# picusb.net
KiCad netlist of a schematic drawn in EAGLE
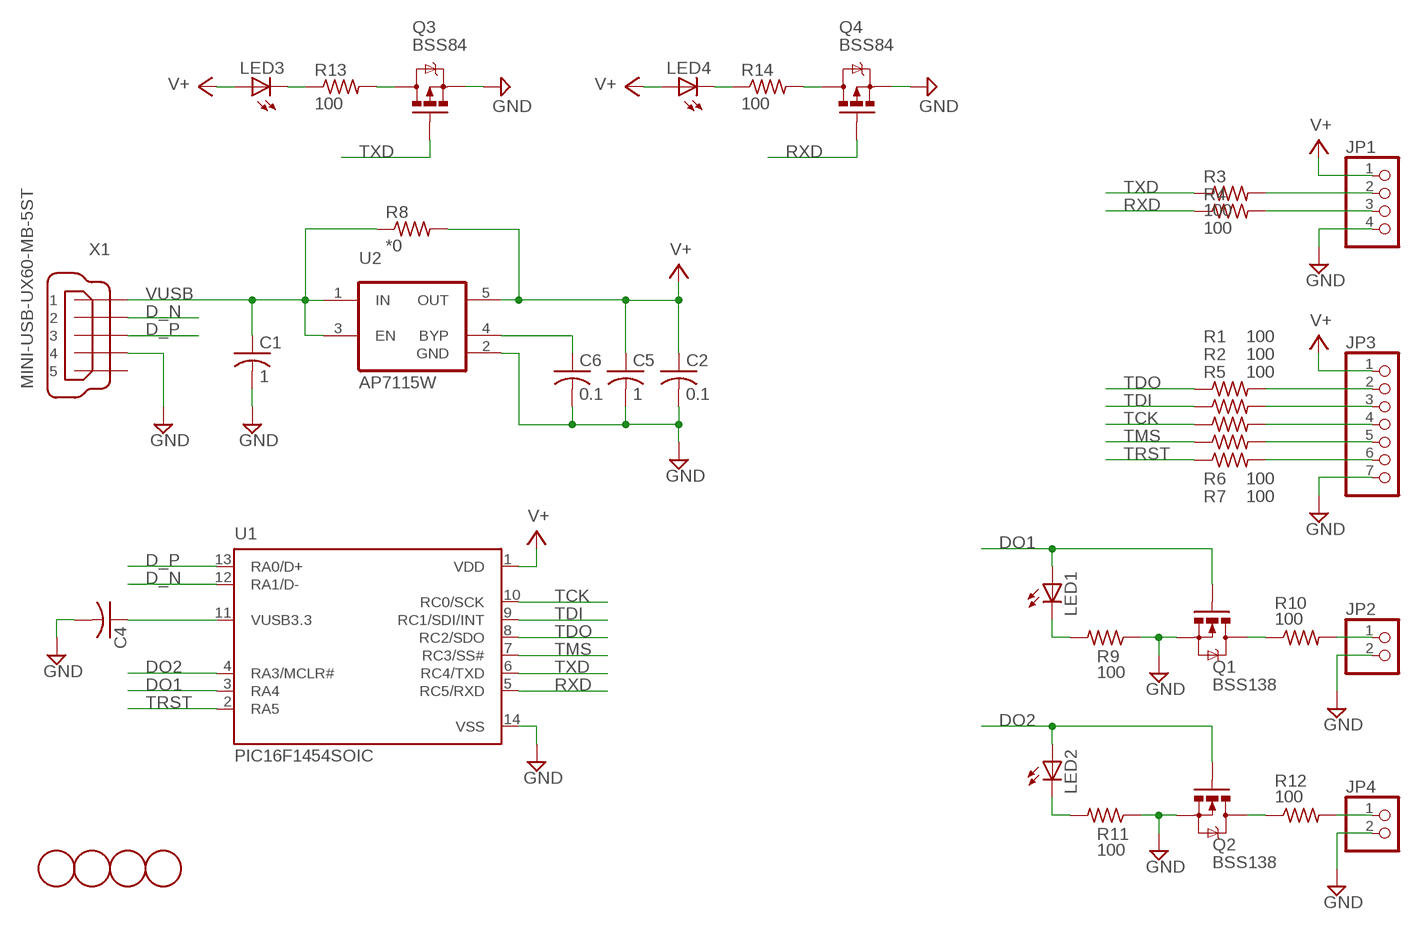
[diagram p0: schematic, sheet 1]

(export (version "E")
  (design (tool "Eeschema 10.0.6"))
  (components
    (comp (ref "C1")
      (value "1")
      (footprint "eagle-import:C0805")
      (libsource (lib "eagle-import") (part "C-USC0805"))
    )
    (comp (ref "C2")
      (value "0.1")
      (footprint "eagle-import:C0805")
      (libsource (lib "eagle-import") (part "C-USC0805"))
    )
    (comp (ref "C4")
      (value "C-USC0805")
      (footprint "eagle-import:C0805")
      (libsource (lib "eagle-import") (part "C-USC0805"))
    )
    (comp (ref "C5")
      (value "1")
      (footprint "eagle-import:C0805")
      (libsource (lib "eagle-import") (part "C-USC0805"))
    )
    (comp (ref "C6")
      (value "0.1")
      (footprint "eagle-import:C0805")
      (libsource (lib "eagle-import") (part "C-USC0805"))
    )
    (comp (ref "JP1")
      (value "PINHD-1X4")
      (footprint "eagle-import:1X04")
      (libsource (lib "eagle-import") (part "PINHD-1X4"))
    )
    (comp (ref "JP2")
      (value "PINHD-1X2")
      (footprint "eagle-import:1X02")
      (libsource (lib "eagle-import") (part "PINHD-1X2"))
    )
    (comp (ref "JP3")
      (value "PINHD-1X7")
      (footprint "eagle-import:1X07")
      (libsource (lib "eagle-import") (part "PINHD-1X7"))
    )
    (comp (ref "JP4")
      (value "PINHD-1X2")
      (footprint "eagle-import:1X02")
      (libsource (lib "eagle-import") (part "PINHD-1X2"))
    )
    (comp (ref "LED1")
      (value "LEDCHIP-LED0805")
      (footprint "eagle-import:CHIP-LED0805")
      (libsource (lib "eagle-import") (part "LEDCHIP-LED0805"))
    )
    (comp (ref "LED2")
      (value "LEDCHIP-LED0805")
      (footprint "eagle-import:CHIP-LED0805")
      (libsource (lib "eagle-import") (part "LEDCHIP-LED0805"))
    )
    (comp (ref "LED3")
      (value "LEDCHIP-LED0805")
      (footprint "eagle-import:CHIP-LED0805")
      (libsource (lib "eagle-import") (part "LEDCHIP-LED0805"))
    )
    (comp (ref "LED4")
      (value "LEDCHIP-LED0805")
      (footprint "eagle-import:CHIP-LED0805")
      (libsource (lib "eagle-import") (part "LEDCHIP-LED0805"))
    )
    (comp (ref "Q1")
      (value "BSS138")
      (footprint "eagle-import:SOT23-3")
      (libsource (lib "eagle-import") (part "MOSFET-NCHANNELSMD"))
    )
    (comp (ref "Q2")
      (value "BSS138")
      (footprint "eagle-import:SOT23-3")
      (libsource (lib "eagle-import") (part "MOSFET-NCHANNELSMD"))
    )
    (comp (ref "Q3")
      (value "BSS84")
      (footprint "eagle-import:SOT23")
      (libsource (lib "eagle-import") (part "MOSFET-PCHANNELSOT23"))
    )
    (comp (ref "Q4")
      (value "BSS84")
      (footprint "eagle-import:SOT23")
      (libsource (lib "eagle-import") (part "MOSFET-PCHANNELSOT23"))
    )
    (comp (ref "R1")
      (value "100")
      (footprint "eagle-import:R0805")
      (libsource (lib "eagle-import") (part "R-US_R0805"))
    )
    (comp (ref "R2")
      (value "100")
      (footprint "eagle-import:R0805")
      (libsource (lib "eagle-import") (part "R-US_R0805"))
    )
    (comp (ref "R3")
      (value "100")
      (footprint "eagle-import:R0805")
      (libsource (lib "eagle-import") (part "R-US_R0805"))
    )
    (comp (ref "R4")
      (value "100")
      (footprint "eagle-import:R0805")
      (libsource (lib "eagle-import") (part "R-US_R0805"))
    )
    (comp (ref "R5")
      (value "100")
      (footprint "eagle-import:R0805")
      (libsource (lib "eagle-import") (part "R-US_R0805"))
    )
    (comp (ref "R6")
      (value "100")
      (footprint "eagle-import:R0805")
      (libsource (lib "eagle-import") (part "R-US_R0805"))
    )
    (comp (ref "R7")
      (value "100")
      (footprint "eagle-import:R0805")
      (libsource (lib "eagle-import") (part "R-US_R0805"))
    )
    (comp (ref "R8")
      (value "*0")
      (footprint "eagle-import:R0805")
      (libsource (lib "eagle-import") (part "R-US_R0805"))
    )
    (comp (ref "R9")
      (value "100")
      (footprint "eagle-import:R0805")
      (libsource (lib "eagle-import") (part "R-US_R0805"))
    )
    (comp (ref "R10")
      (value "100")
      (footprint "eagle-import:R0805")
      (libsource (lib "eagle-import") (part "R-US_R0805"))
    )
    (comp (ref "R11")
      (value "100")
      (footprint "eagle-import:R0805")
      (libsource (lib "eagle-import") (part "R-US_R0805"))
    )
    (comp (ref "R12")
      (value "100")
      (footprint "eagle-import:R0805")
      (libsource (lib "eagle-import") (part "R-US_R0805"))
    )
    (comp (ref "R13")
      (value "100")
      (footprint "eagle-import:R0805")
      (libsource (lib "eagle-import") (part "R-US_R0805"))
    )
    (comp (ref "R14")
      (value "100")
      (footprint "eagle-import:R0805")
      (libsource (lib "eagle-import") (part "R-US_R0805"))
    )
    (comp (ref "U$1")
      (value "MOUNTING_HOLENO_4")
      (footprint "eagle-import:HOLE_MTG_NO4")
      (libsource (lib "eagle-import") (part "MOUNTING_HOLENO_4"))
    )
    (comp (ref "U$2")
      (value "MOUNTING_HOLENO_4")
      (footprint "eagle-import:HOLE_MTG_NO4")
      (libsource (lib "eagle-import") (part "MOUNTING_HOLENO_4"))
    )
    (comp (ref "U$3")
      (value "MOUNTING_HOLENO_4")
      (footprint "eagle-import:HOLE_MTG_NO4")
      (libsource (lib "eagle-import") (part "MOUNTING_HOLENO_4"))
    )
    (comp (ref "U$4")
      (value "MOUNTING_HOLENO_4")
      (footprint "eagle-import:HOLE_MTG_NO4")
      (libsource (lib "eagle-import") (part "MOUNTING_HOLENO_4"))
    )
    (comp (ref "U1")
      (value "PIC16F1454SOIC")
      (footprint "eagle-import:SOIC14")
      (libsource (lib "eagle-import") (part "PIC16F1454SOIC"))
    )
    (comp (ref "U2")
      (value "AP7115W")
      (footprint "eagle-import:SOT25")
      (libsource (lib "eagle-import") (part "AP7115W"))
    )
    (comp (ref "X1")
      (value "MINI-USB-UX60-MB-5ST")
      (footprint "eagle-import:UX60-MB-5ST")
      (libsource (lib "eagle-import") (part "MINI-USB-UX60-MB-5ST"))
    )
  )
  (nets
    (net (code "1") (name "/DO1") (class "Default")
      (node (ref "LED1") (pin "A") (pinfunction "A_A") (pintype "passive"))
      (node (ref "Q1") (pin "1") (pinfunction "G_1") (pintype "passive"))
      (node (ref "U1") (pin "3") (pinfunction "RA4_3") (pintype "bidirectional"))
    )
    (net (code "2") (name "/DO2") (class "Default")
      (node (ref "LED2") (pin "A") (pinfunction "A_A") (pintype "passive"))
      (node (ref "Q2") (pin "1") (pinfunction "G_1") (pintype "passive"))
      (node (ref "U1") (pin "4") (pinfunction "RA3/MCLR#_4") (pintype "bidirectional"))
    )
    (net (code "3") (name "/D_N") (class "Default")
      (node (ref "U1") (pin "12") (pinfunction "RA1/D-_12") (pintype "bidirectional"))
      (node (ref "X1") (pin "2") (pinfunction "2_2") (pintype "input"))
    )
    (net (code "4") (name "/D_P") (class "Default")
      (node (ref "U1") (pin "13") (pinfunction "RA0/D+_13") (pintype "bidirectional"))
      (node (ref "X1") (pin "3") (pinfunction "3_3") (pintype "input"))
    )
    (net (code "5") (name "/RXD") (class "Default")
      (node (ref "Q4") (pin "1") (pinfunction "G_1") (pintype "passive"))
      (node (ref "R4") (pin "1") (pinfunction "1_1") (pintype "passive"))
      (node (ref "U1") (pin "5") (pinfunction "RC5/RXD_5") (pintype "bidirectional"))
    )
    (net (code "6") (name "/TCK") (class "Default")
      (node (ref "R5") (pin "1") (pinfunction "1_1") (pintype "passive"))
      (node (ref "U1") (pin "10") (pinfunction "RC0/SCK_10") (pintype "bidirectional"))
    )
    (net (code "7") (name "/TDI") (class "Default")
      (node (ref "R2") (pin "1") (pinfunction "1_1") (pintype "passive"))
      (node (ref "U1") (pin "9") (pinfunction "RC1/SDI/INT_9") (pintype "bidirectional"))
    )
    (net (code "8") (name "/TDO") (class "Default")
      (node (ref "R1") (pin "1") (pinfunction "1_1") (pintype "passive"))
      (node (ref "U1") (pin "8") (pinfunction "RC2/SDO_8") (pintype "bidirectional"))
    )
    (net (code "9") (name "/TMS") (class "Default")
      (node (ref "R6") (pin "1") (pinfunction "1_1") (pintype "passive"))
      (node (ref "U1") (pin "7") (pinfunction "RC3/SS#_7") (pintype "bidirectional"))
    )
    (net (code "10") (name "/TRST") (class "Default")
      (node (ref "R7") (pin "1") (pinfunction "1_1") (pintype "passive"))
      (node (ref "U1") (pin "2") (pinfunction "RA5_2") (pintype "bidirectional"))
    )
    (net (code "11") (name "/TXD") (class "Default")
      (node (ref "Q3") (pin "1") (pinfunction "G_1") (pintype "passive"))
      (node (ref "R3") (pin "1") (pinfunction "1_1") (pintype "passive"))
      (node (ref "U1") (pin "6") (pinfunction "RC4/TXD_6") (pintype "bidirectional"))
    )
    (net (code "12") (name "/VUSB") (class "Default")
      (node (ref "C1") (pin "1") (pinfunction "1_1") (pintype "passive"))
      (node (ref "R8") (pin "1") (pinfunction "1_1") (pintype "passive"))
      (node (ref "U2") (pin "1") (pinfunction "IN_1") (pintype "power_in"))
      (node (ref "U2") (pin "3") (pinfunction "EN_3") (pintype "bidirectional"))
      (node (ref "X1") (pin "1") (pinfunction "1_1") (pintype "input"))
    )
    (net (code "13") (name "GND") (class "Default")
      (node (ref "C1") (pin "2") (pinfunction "2_2") (pintype "passive"))
      (node (ref "C2") (pin "2") (pinfunction "2_2") (pintype "passive"))
      (node (ref "C4") (pin "2") (pinfunction "2_2") (pintype "passive"))
      (node (ref "C5") (pin "2") (pinfunction "2_2") (pintype "passive"))
      (node (ref "C6") (pin "2") (pinfunction "2_2") (pintype "passive"))
      (node (ref "JP1") (pin "4") (pinfunction "4_4") (pintype "passive"))
      (node (ref "JP2") (pin "2") (pinfunction "2_2") (pintype "passive"))
      (node (ref "JP3") (pin "7") (pinfunction "7_7") (pintype "passive"))
      (node (ref "JP4") (pin "2") (pinfunction "2_2") (pintype "passive"))
      (node (ref "Q1") (pin "2") (pinfunction "S_2") (pintype "passive"))
      (node (ref "Q2") (pin "2") (pinfunction "S_2") (pintype "passive"))
      (node (ref "Q3") (pin "2") (pinfunction "S_2") (pintype "passive"))
      (node (ref "Q4") (pin "2") (pinfunction "S_2") (pintype "passive"))
      (node (ref "R11") (pin "1") (pinfunction "1_1") (pintype "passive"))
      (node (ref "R9") (pin "1") (pinfunction "1_1") (pintype "passive"))
      (node (ref "U1") (pin "14") (pinfunction "VSS_14") (pintype "power_in"))
      (node (ref "U2") (pin "2") (pinfunction "GND_2") (pintype "power_in"))
      (node (ref "X1") (pin "4") (pinfunction "4_4") (pintype "input"))
    )
    (net (code "14") (name "Net-(JP1-Pad2)") (class "Default")
      (node (ref "JP1") (pin "2") (pinfunction "2_2") (pintype "passive"))
      (node (ref "R3") (pin "2") (pinfunction "2_2") (pintype "passive"))
    )
    (net (code "15") (name "Net-(JP1-Pad3)") (class "Default")
      (node (ref "JP1") (pin "3") (pinfunction "3_3") (pintype "passive"))
      (node (ref "R4") (pin "2") (pinfunction "2_2") (pintype "passive"))
    )
    (net (code "16") (name "Net-(JP2-Pad1)") (class "Default")
      (node (ref "JP2") (pin "1") (pinfunction "1_1") (pintype "passive"))
      (node (ref "R10") (pin "2") (pinfunction "2_2") (pintype "passive"))
    )
    (net (code "17") (name "Net-(JP3-Pad2)") (class "Default")
      (node (ref "JP3") (pin "2") (pinfunction "2_2") (pintype "passive"))
      (node (ref "R1") (pin "2") (pinfunction "2_2") (pintype "passive"))
    )
    (net (code "18") (name "Net-(JP3-Pad3)") (class "Default")
      (node (ref "JP3") (pin "3") (pinfunction "3_3") (pintype "passive"))
      (node (ref "R2") (pin "2") (pinfunction "2_2") (pintype "passive"))
    )
    (net (code "19") (name "Net-(JP3-Pad4)") (class "Default")
      (node (ref "JP3") (pin "4") (pinfunction "4_4") (pintype "passive"))
      (node (ref "R5") (pin "2") (pinfunction "2_2") (pintype "passive"))
    )
    (net (code "20") (name "Net-(JP3-Pad5)") (class "Default")
      (node (ref "JP3") (pin "5") (pinfunction "5_5") (pintype "passive"))
      (node (ref "R6") (pin "2") (pinfunction "2_2") (pintype "passive"))
    )
    (net (code "21") (name "Net-(JP3-Pad6)") (class "Default")
      (node (ref "JP3") (pin "6") (pinfunction "6_6") (pintype "passive"))
      (node (ref "R7") (pin "2") (pinfunction "2_2") (pintype "passive"))
    )
    (net (code "22") (name "Net-(JP4-Pad1)") (class "Default")
      (node (ref "JP4") (pin "1") (pinfunction "1_1") (pintype "passive"))
      (node (ref "R12") (pin "2") (pinfunction "2_2") (pintype "passive"))
    )
    (net (code "23") (name "Net-(LED1-PadC)") (class "Default")
      (node (ref "LED1") (pin "C") (pinfunction "C_C") (pintype "passive"))
      (node (ref "R9") (pin "2") (pinfunction "2_2") (pintype "passive"))
    )
    (net (code "24") (name "Net-(LED2-PadC)") (class "Default")
      (node (ref "LED2") (pin "C") (pinfunction "C_C") (pintype "passive"))
      (node (ref "R11") (pin "2") (pinfunction "2_2") (pintype "passive"))
    )
    (net (code "25") (name "Net-(LED3-PadC)") (class "Default")
      (node (ref "LED3") (pin "C") (pinfunction "C_C") (pintype "passive"))
      (node (ref "R13") (pin "1") (pinfunction "1_1") (pintype "passive"))
    )
    (net (code "26") (name "Net-(LED4-PadC)") (class "Default")
      (node (ref "LED4") (pin "C") (pinfunction "C_C") (pintype "passive"))
      (node (ref "R14") (pin "1") (pinfunction "1_1") (pintype "passive"))
    )
    (net (code "27") (name "Net-(Q1-D)") (class "Default")
      (node (ref "Q1") (pin "3") (pinfunction "D_3") (pintype "passive"))
      (node (ref "R10") (pin "1") (pinfunction "1_1") (pintype "passive"))
    )
    (net (code "28") (name "Net-(Q2-D)") (class "Default")
      (node (ref "Q2") (pin "3") (pinfunction "D_3") (pintype "passive"))
      (node (ref "R12") (pin "1") (pinfunction "1_1") (pintype "passive"))
    )
    (net (code "29") (name "Net-(Q3-D)") (class "Default")
      (node (ref "Q3") (pin "3") (pinfunction "D_3") (pintype "passive"))
      (node (ref "R13") (pin "2") (pinfunction "2_2") (pintype "passive"))
    )
    (net (code "30") (name "Net-(Q4-D)") (class "Default")
      (node (ref "Q4") (pin "3") (pinfunction "D_3") (pintype "passive"))
      (node (ref "R14") (pin "2") (pinfunction "2_2") (pintype "passive"))
    )
    (net (code "31") (name "Net-(U1-VUSB3.3)") (class "Default")
      (node (ref "C4") (pin "1") (pinfunction "1_1") (pintype "passive"))
      (node (ref "U1") (pin "11") (pinfunction "VUSB3.3_11") (pintype "power_in"))
    )
    (net (code "32") (name "Net-(U2-BYP)") (class "Default")
      (node (ref "C6") (pin "1") (pinfunction "1_1") (pintype "passive"))
      (node (ref "U2") (pin "4") (pinfunction "BYP_4") (pintype "passive"))
    )
    (net (code "33") (name "V+") (class "Default")
      (node (ref "C2") (pin "1") (pinfunction "1_1") (pintype "passive"))
      (node (ref "C5") (pin "1") (pinfunction "1_1") (pintype "passive"))
      (node (ref "JP1") (pin "1") (pinfunction "1_1") (pintype "passive"))
      (node (ref "JP3") (pin "1") (pinfunction "1_1") (pintype "passive"))
      (node (ref "LED3") (pin "A") (pinfunction "A_A") (pintype "passive"))
      (node (ref "LED4") (pin "A") (pinfunction "A_A") (pintype "passive"))
      (node (ref "R8") (pin "2") (pinfunction "2_2") (pintype "passive"))
      (node (ref "U1") (pin "1") (pinfunction "VDD_1") (pintype "power_in"))
      (node (ref "U2") (pin "5") (pinfunction "OUT_5") (pintype "power_in"))
    )
    (net (code "34") (name "unconnected-(X1-Pad5)") (class "Default")
      (node (ref "X1") (pin "5") (pinfunction "5_5") (pintype "input"))
    )
  )
)
